# mood_ring.net
KiCad netlist of a schematic drawn in EAGLE
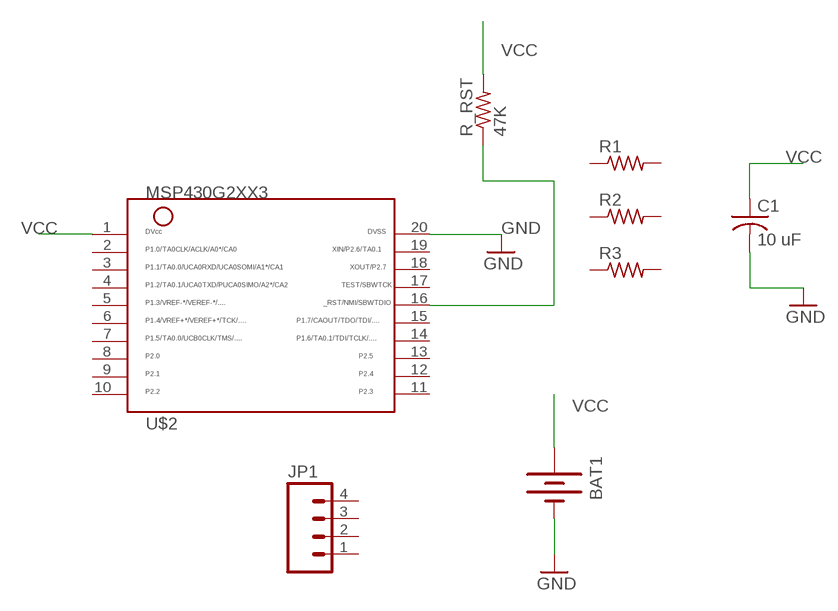
[diagram p0: schematic, sheet 1]

(export (version "E")
  (design (tool "Eeschema 10.0.6"))
  (components
    (comp (ref "BAT1")
      (value "BATTERYBU2032SM")
      (footprint "eagle-import:BU2032SM")
      (libsource (lib "eagle-import") (part "BATTERYBU2032SM"))
    )
    (comp (ref "C1")
      (value "10 uF")
      (footprint "eagle-import:C1206")
      (libsource (lib "eagle-import") (part "C-USC1206"))
    )
    (comp (ref "JP1")
      (value "M04LOCK")
      (footprint "eagle-import:1X04_LOCK")
      (libsource (lib "eagle-import") (part "M04LOCK"))
    )
    (comp (ref "R1")
      (value "R-US_R1206")
      (footprint "eagle-import:R1206")
      (libsource (lib "eagle-import") (part "R-US_R1206"))
    )
    (comp (ref "R2")
      (value "R-US_R1206")
      (footprint "eagle-import:R1206")
      (libsource (lib "eagle-import") (part "R-US_R1206"))
    )
    (comp (ref "R3")
      (value "R-US_R1206")
      (footprint "eagle-import:R1206")
      (libsource (lib "eagle-import") (part "R-US_R1206"))
    )
    (comp (ref "R_RST")
      (value "47K")
      (footprint "eagle-import:R1206")
      (libsource (lib "eagle-import") (part "R-US_R1206"))
    )
    (comp (ref "U$2")
      (value "MSP430G2XX3TSSOP")
      (footprint "eagle-import:PW20")
      (libsource (lib "eagle-import") (part "MSP430G2XX3TSSOP"))
    )
  )
  (nets
    (net (code "1") (name "/VCC") (class "Default")
      (node (ref "BAT1") (pin "P$1") (pinfunction "+_P$1") (pintype "power_in"))
      (node (ref "C1") (pin "1") (pinfunction "1_1") (pintype "passive"))
      (node (ref "R_RST") (pin "2") (pinfunction "2_2") (pintype "passive"))
      (node (ref "U$2") (pin "1") (pinfunction "1_1") (pintype "bidirectional"))
    )
    (net (code "2") (name "GND") (class "Default")
      (node (ref "BAT1") (pin "P$2") (pinfunction "-_P$2") (pintype "power_in"))
      (node (ref "C1") (pin "2") (pinfunction "2_2") (pintype "passive"))
      (node (ref "U$2") (pin "20") (pinfunction "20_20") (pintype "bidirectional"))
    )
    (net (code "3") (name "Net-(R_RST-Pad1)") (class "Default")
      (node (ref "R_RST") (pin "1") (pinfunction "1_1") (pintype "passive"))
      (node (ref "U$2") (pin "16") (pinfunction "16_16") (pintype "bidirectional"))
    )
    (net (code "4") (name "unconnected-(JP1-Pad1)") (class "Default")
      (node (ref "JP1") (pin "1") (pinfunction "1_1") (pintype "passive"))
    )
    (net (code "5") (name "unconnected-(JP1-Pad2)") (class "Default")
      (node (ref "JP1") (pin "2") (pinfunction "2_2") (pintype "passive"))
    )
    (net (code "6") (name "unconnected-(JP1-Pad3)") (class "Default")
      (node (ref "JP1") (pin "3") (pinfunction "3_3") (pintype "passive"))
    )
    (net (code "7") (name "unconnected-(JP1-Pad4)") (class "Default")
      (node (ref "JP1") (pin "4") (pinfunction "4_4") (pintype "passive"))
    )
    (net (code "8") (name "unconnected-(R1-Pad1)") (class "Default")
      (node (ref "R1") (pin "1") (pinfunction "1_1") (pintype "passive"))
    )
    (net (code "9") (name "unconnected-(R1-Pad2)") (class "Default")
      (node (ref "R1") (pin "2") (pinfunction "2_2") (pintype "passive"))
    )
    (net (code "10") (name "unconnected-(R2-Pad1)") (class "Default")
      (node (ref "R2") (pin "1") (pinfunction "1_1") (pintype "passive"))
    )
    (net (code "11") (name "unconnected-(R2-Pad2)") (class "Default")
      (node (ref "R2") (pin "2") (pinfunction "2_2") (pintype "passive"))
    )
    (net (code "12") (name "unconnected-(R3-Pad1)") (class "Default")
      (node (ref "R3") (pin "1") (pinfunction "1_1") (pintype "passive"))
    )
    (net (code "13") (name "unconnected-(R3-Pad2)") (class "Default")
      (node (ref "R3") (pin "2") (pinfunction "2_2") (pintype "passive"))
    )
    (net (code "14") (name "unconnected-(U$2-Pad2)") (class "Default")
      (node (ref "U$2") (pin "2") (pinfunction "2_2") (pintype "bidirectional"))
    )
    (net (code "15") (name "unconnected-(U$2-Pad3)") (class "Default")
      (node (ref "U$2") (pin "3") (pinfunction "3_3") (pintype "bidirectional"))
    )
    (net (code "16") (name "unconnected-(U$2-Pad4)") (class "Default")
      (node (ref "U$2") (pin "4") (pinfunction "4_4") (pintype "bidirectional"))
    )
    (net (code "17") (name "unconnected-(U$2-Pad5)") (class "Default")
      (node (ref "U$2") (pin "5") (pinfunction "5_5") (pintype "bidirectional"))
    )
    (net (code "18") (name "unconnected-(U$2-Pad6)") (class "Default")
      (node (ref "U$2") (pin "6") (pinfunction "6_6") (pintype "bidirectional"))
    )
    (net (code "19") (name "unconnected-(U$2-Pad7)") (class "Default")
      (node (ref "U$2") (pin "7") (pinfunction "7_7") (pintype "bidirectional"))
    )
    (net (code "20") (name "unconnected-(U$2-Pad8)") (class "Default")
      (node (ref "U$2") (pin "8") (pinfunction "8_8") (pintype "bidirectional"))
    )
    (net (code "21") (name "unconnected-(U$2-Pad9)") (class "Default")
      (node (ref "U$2") (pin "9") (pinfunction "9_9") (pintype "bidirectional"))
    )
    (net (code "22") (name "unconnected-(U$2-Pad10)") (class "Default")
      (node (ref "U$2") (pin "10") (pinfunction "10_10") (pintype "bidirectional"))
    )
    (net (code "23") (name "unconnected-(U$2-Pad11)") (class "Default")
      (node (ref "U$2") (pin "11") (pinfunction "11_11") (pintype "bidirectional"))
    )
    (net (code "24") (name "unconnected-(U$2-Pad12)") (class "Default")
      (node (ref "U$2") (pin "12") (pinfunction "12_12") (pintype "bidirectional"))
    )
    (net (code "25") (name "unconnected-(U$2-Pad13)") (class "Default")
      (node (ref "U$2") (pin "13") (pinfunction "13_13") (pintype "bidirectional"))
    )
    (net (code "26") (name "unconnected-(U$2-Pad14)") (class "Default")
      (node (ref "U$2") (pin "14") (pinfunction "14_14") (pintype "bidirectional"))
    )
    (net (code "27") (name "unconnected-(U$2-Pad15)") (class "Default")
      (node (ref "U$2") (pin "15") (pinfunction "15_15") (pintype "bidirectional"))
    )
    (net (code "28") (name "unconnected-(U$2-Pad17)") (class "Default")
      (node (ref "U$2") (pin "17") (pinfunction "17_17") (pintype "bidirectional"))
    )
    (net (code "29") (name "unconnected-(U$2-Pad18)") (class "Default")
      (node (ref "U$2") (pin "18") (pinfunction "18_18") (pintype "bidirectional"))
    )
    (net (code "30") (name "unconnected-(U$2-Pad19)") (class "Default")
      (node (ref "U$2") (pin "19") (pinfunction "19_19") (pintype "bidirectional"))
    )
  )
)
